# aboutlove.net
KiCad netlist of a schematic drawn in Altium Designer
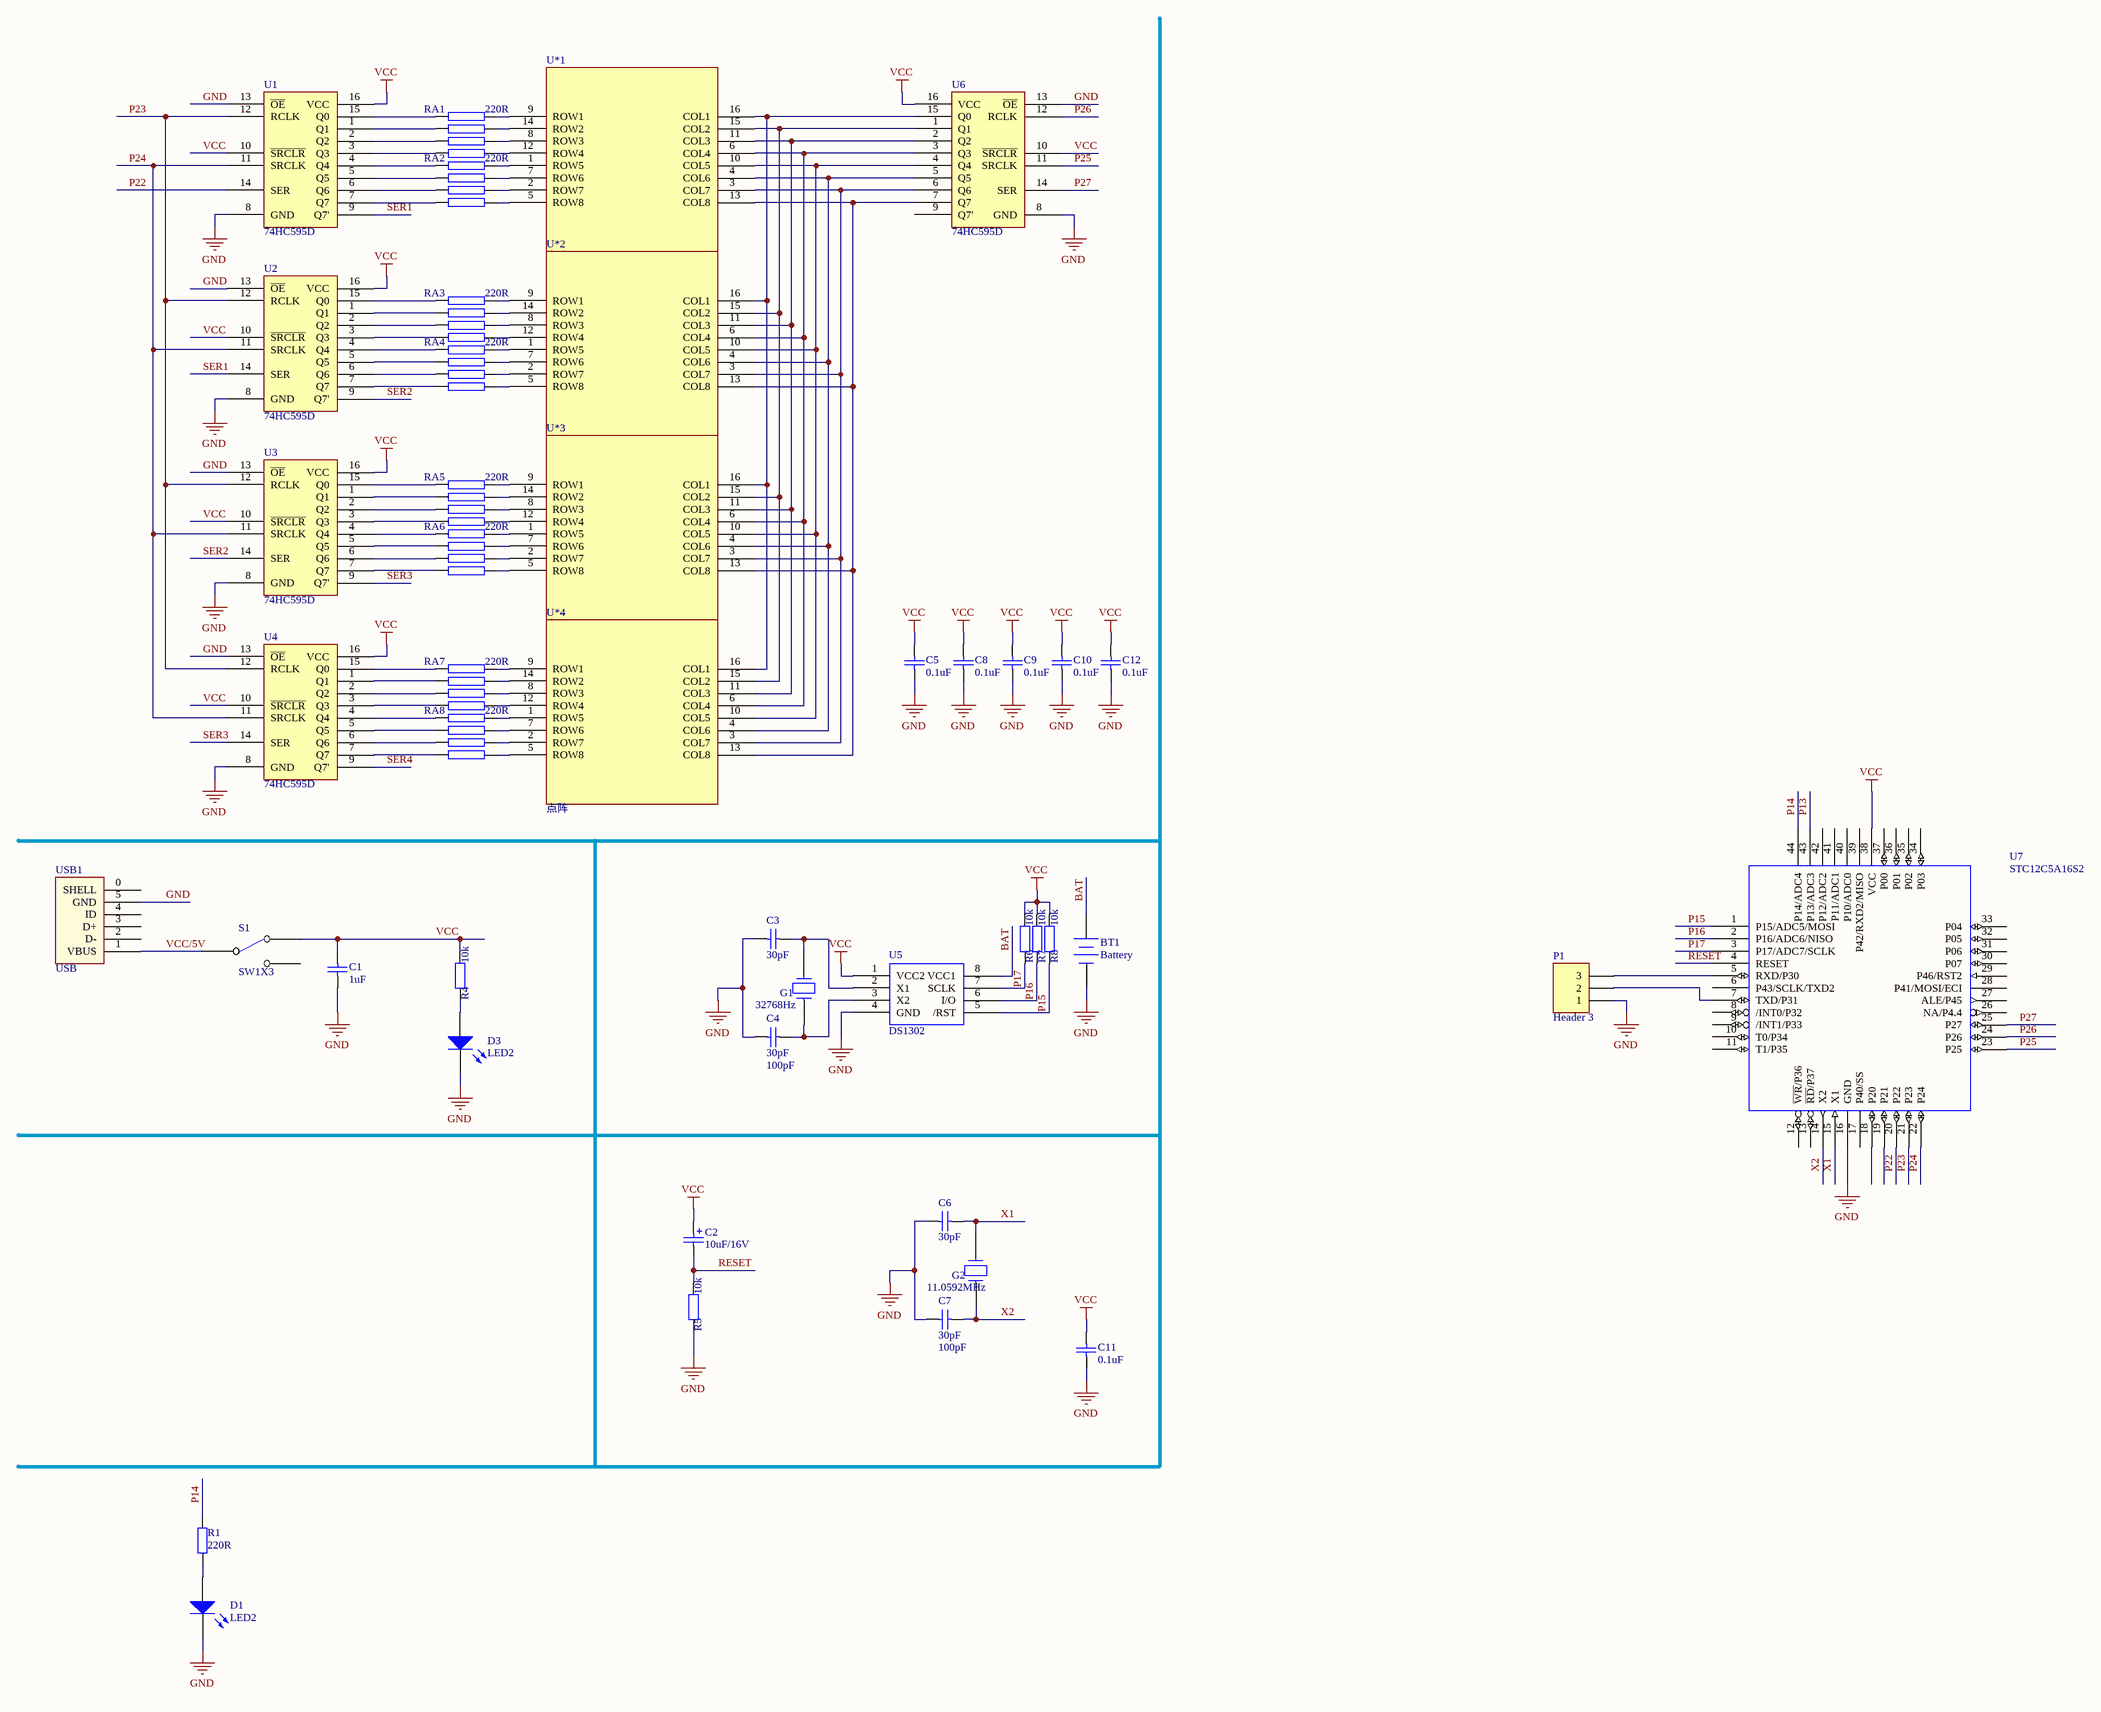
[diagram p0: aboutlove.SchDoc]

(export (version "E")
  (design (tool "Eeschema 10.0.6"))
  (components
    (comp (ref "BT1")
      (value "Battery")
      (footprint "BAT-CR1220")
      (description "Multicell Battery")
      (fields (field (name "PUBLISHER") "Altium Limited"))
      (libsource (lib "Miscellaneous Devices") (part "Battery"))
    )
    (comp (ref "C1")
      (value "1uF")
      (footprint "0805")
      (description "Capacitor")
      (fields (field (name "PUBLISHER") "Altium Limited"))
      (libsource (lib "Miscellaneous Devices") (part "Cap"))
    )
    (comp (ref "C2")
      (value "10uF/16V")
      (footprint "RB.1/.2A")
      (description "Polarized Capacitor (Axial)")
      (fields (field (name "PUBLISHER") "Altium Limited"))
      (libsource (lib "Miscellaneous Devices") (part "Cap Pol2"))
    )
    (comp (ref "C3")
      (value "30pF")
      (footprint "0603_SMALL")
      (description "Capacitor")
      (fields (field (name "PUBLISHER") "Altium Limited"))
      (libsource (lib "Miscellaneous Devices") (part "Cap"))
    )
    (comp (ref "C4")
      (value "30pF")
      (footprint "0603_SMALL")
      (description "Capacitor")
      (fields (field (name "ALTIUM_VALUE") "100pF") (field (name "PUBLISHER") "Altium Limited"))
      (libsource (lib "Miscellaneous Devices") (part "Cap"))
    )
    (comp (ref "C5")
      (value "0.1uF")
      (footprint "0603_SMALL")
      (description "Capacitor")
      (fields (field (name "PUBLISHER") "Altium Limited"))
      (libsource (lib "Miscellaneous Devices") (part "Cap"))
    )
    (comp (ref "C6")
      (value "30pF")
      (footprint "0603_SMALL")
      (description "Capacitor")
      (fields (field (name "PUBLISHER") "Altium Limited"))
      (libsource (lib "Miscellaneous Devices") (part "Cap"))
    )
    (comp (ref "C7")
      (value "30pF")
      (footprint "0603_SMALL")
      (description "Capacitor")
      (fields (field (name "ALTIUM_VALUE") "100pF") (field (name "PUBLISHER") "Altium Limited"))
      (libsource (lib "Miscellaneous Devices") (part "Cap"))
    )
    (comp (ref "C8")
      (value "0.1uF")
      (footprint "0603_SMALL")
      (description "Capacitor")
      (fields (field (name "PUBLISHER") "Altium Limited"))
      (libsource (lib "Miscellaneous Devices") (part "Cap"))
    )
    (comp (ref "C9")
      (value "0.1uF")
      (footprint "0603_SMALL")
      (description "Capacitor")
      (fields (field (name "PUBLISHER") "Altium Limited"))
      (libsource (lib "Miscellaneous Devices") (part "Cap"))
    )
    (comp (ref "C10")
      (value "0.1uF")
      (footprint "0603_SMALL")
      (description "Capacitor")
      (fields (field (name "PUBLISHER") "Altium Limited"))
      (libsource (lib "Miscellaneous Devices") (part "Cap"))
    )
    (comp (ref "C11")
      (value "0.1uF")
      (footprint "0603_SMALL")
      (description "Capacitor")
      (fields (field (name "PUBLISHER") "Altium Limited"))
      (libsource (lib "Miscellaneous Devices") (part "Cap"))
    )
    (comp (ref "C12")
      (value "0.1uF")
      (footprint "0603_SMALL")
      (description "Capacitor")
      (fields (field (name "PUBLISHER") "Altium Limited"))
      (libsource (lib "Miscellaneous Devices") (part "Cap"))
    )
    (comp (ref "D1")
      (value "LED2")
      (footprint "LED0805")
      (description "Typical RED, GREEN, YELLOW, AMBER GaAs LED")
      (fields (field (name "PUBLISHER") "Altium Limited"))
      (libsource (lib "Miscellaneous Devices") (part "LED2"))
    )
    (comp (ref "D3")
      (value "LED2")
      (footprint "LED0805")
      (description "Typical RED, GREEN, YELLOW, AMBER GaAs LED")
      (fields (field (name "PUBLISHER") "Altium Limited"))
      (libsource (lib "Miscellaneous Devices") (part "LED2"))
    )
    (comp (ref "G1")
      (value "32768Hz")
      (footprint "SIP2")
      (description "Crystal")
      (libsource (lib "12C5A60S2") (part "CRYSTAL"))
    )
    (comp (ref "G2")
      (value "11.0592MHz")
      (footprint "XTAL1_ARC")
      (description "Crystal")
      (libsource (lib "12C5A60S2") (part "CRYSTAL"))
    )
    (comp (ref "P1")
      (value "Header 3")
      (footprint "HDR1X3")
      (description "Header, 3-Pin")
      (fields (field (name "PUBLISHER") "Altium Limited"))
      (libsource (lib "Miscellaneous Connectors") (part "Header 3"))
    )
    (comp (ref "R1")
      (value "220R")
      (footprint "0603_SMALL")
      (description "Resistor")
      (fields (field (name "PUBLISHER") "Altium Limited"))
      (libsource (lib "Miscellaneous Devices") (part "Res2"))
    )
    (comp (ref "R4")
      (value "10k")
      (footprint "0805")
      (description "Resistor")
      (fields (field (name "PUBLISHER") "Altium Limited"))
      (libsource (lib "") (part "Res2_1"))
    )
    (comp (ref "R5")
      (value "10k")
      (footprint "0603_SMALL")
      (description "Resistor")
      (fields (field (name "PUBLISHER") "Altium Limited"))
      (libsource (lib "") (part "Res2_1"))
    )
    (comp (ref "R6")
      (value "10k")
      (footprint "0603_SMALL")
      (description "Resistor")
      (fields (field (name "PUBLISHER") "Altium Limited"))
      (libsource (lib "") (part "Res2_1"))
    )
    (comp (ref "R7")
      (value "10k")
      (footprint "0603_SMALL")
      (description "Resistor")
      (fields (field (name "PUBLISHER") "Altium Limited"))
      (libsource (lib "") (part "Res2_1"))
    )
    (comp (ref "R8")
      (value "10k")
      (footprint "0603_SMALL")
      (description "Resistor")
      (fields (field (name "PUBLISHER") "Altium Limited"))
      (libsource (lib "") (part "Res2_1"))
    )
    (comp (ref "RA1") (value "220R") (footprint "NR4_L") (libsource (lib "12C5A60S2") (part "NR4")))
    (comp (ref "RA2") (value "220R") (footprint "NR4_L") (libsource (lib "12C5A60S2") (part "NR4")))
    (comp (ref "RA3") (value "220R") (footprint "NR4_L") (libsource (lib "12C5A60S2") (part "NR4")))
    (comp (ref "RA4") (value "220R") (footprint "NR4_L") (libsource (lib "12C5A60S2") (part "NR4")))
    (comp (ref "RA5") (value "220R") (footprint "NR4_L") (libsource (lib "12C5A60S2") (part "NR4")))
    (comp (ref "RA6") (value "220R") (footprint "NR4_L") (libsource (lib "12C5A60S2") (part "NR4")))
    (comp (ref "RA7") (value "220R") (footprint "NR4_L") (libsource (lib "12C5A60S2") (part "NR4")))
    (comp (ref "RA8") (value "220R") (footprint "NR4_L") (libsource (lib "12C5A60S2") (part "NR4")))
    (comp (ref "S1") (value "SW1X3") (footprint "SW1X3") (libsource (lib "SCHS") (part "SW1X3")))
    (comp (ref "U*1") (value "点阵") (footprint "点阵") (libsource (lib "Jack_SCHS") (part "点阵屏")))
    (comp (ref "U*2") (value "点阵") (footprint "点阵") (libsource (lib "Jack_SCHS") (part "点阵屏")))
    (comp (ref "U*3") (value "点阵") (footprint "点阵") (libsource (lib "Jack_SCHS") (part "点阵屏")))
    (comp (ref "U*4") (value "点阵") (footprint "点阵") (libsource (lib "Jack_SCHS") (part "点阵屏")))
    (comp (ref "U1") (value "74HC595D") (footprint "SOP16") (libsource (lib "") (part "74HC595D_1")))
    (comp (ref "U2") (value "74HC595D") (footprint "SOP16") (libsource (lib "") (part "74HC595D_1")))
    (comp (ref "U3") (value "74HC595D") (footprint "SOP16") (libsource (lib "") (part "74HC595D_1")))
    (comp (ref "U4") (value "74HC595D") (footprint "SOP16") (libsource (lib "") (part "74HC595D_1")))
    (comp (ref "U5") (value "DS1302") (footprint "SOP8") (libsource (lib "SCHS") (part "DS1302")))
    (comp (ref "U6") (value "74HC595D") (footprint "SOP16") (libsource (lib "Jack_SCHS") (part "74HC595D")))
    (comp (ref "U7")
      (value "STC12C5A16S2")
      (footprint "TQFP44")
      (libsource (lib "12C5A60S2") (part "STC12C5A08S2"))
    )
    (comp (ref "USB1") (value "USB") (footprint "USB-MINI") (libsource (lib "元器件封装") (part "USB")))
  )
  (nets
    (net (code "1") (name "/BAT") (class "Default")
      (node (ref "BT1") (pin "1") (pinfunction "+_1") (pintype "passive"))
      (node (ref "U5") (pin "8") (pinfunction "VCC1_8") (pintype "passive"))
    )
    (net (code "2") (name "/P13") (class "Default")
      (node (ref "U7") (pin "43") (pinfunction "P13/ADC3_43") (pintype "passive"))
    )
    (net (code "3") (name "/P14") (class "Default")
      (node (ref "R1") (pin "1") (pinfunction "1_1") (pintype "passive"))
      (node (ref "U7") (pin "44") (pinfunction "P14/ADC4_44") (pintype "passive"))
    )
    (net (code "4") (name "/P15") (class "Default")
      (node (ref "R8") (pin "1") (pinfunction "1_1") (pintype "passive"))
      (node (ref "U5") (pin "5") (pinfunction "/RST_5") (pintype "passive"))
      (node (ref "U7") (pin "1") (pinfunction "P15/ADC5/MOSI_1") (pintype "passive"))
    )
    (net (code "5") (name "/P16") (class "Default")
      (node (ref "R7") (pin "1") (pinfunction "1_1") (pintype "passive"))
      (node (ref "U5") (pin "6") (pinfunction "I/O_6") (pintype "passive"))
      (node (ref "U7") (pin "2") (pinfunction "P16/ADC6/NISO_2") (pintype "passive"))
    )
    (net (code "6") (name "/P17") (class "Default")
      (node (ref "R6") (pin "1") (pinfunction "1_1") (pintype "passive"))
      (node (ref "U5") (pin "7") (pinfunction "SCLK_7") (pintype "passive"))
      (node (ref "U7") (pin "3") (pinfunction "P17/ADC7/SCLK_3") (pintype "passive"))
    )
    (net (code "7") (name "/P22") (class "Default")
      (node (ref "U1") (pin "14") (pinfunction "SER_14") (pintype "passive"))
      (node (ref "U7") (pin "20") (pinfunction "P22_20") (pintype "bidirectional"))
    )
    (net (code "8") (name "/P23") (class "Default")
      (node (ref "U1") (pin "12") (pinfunction "RCLK_12") (pintype "passive"))
      (node (ref "U2") (pin "12") (pinfunction "RCLK_12") (pintype "passive"))
      (node (ref "U3") (pin "12") (pinfunction "RCLK_12") (pintype "passive"))
      (node (ref "U4") (pin "12") (pinfunction "RCLK_12") (pintype "passive"))
      (node (ref "U7") (pin "21") (pinfunction "P23_21") (pintype "bidirectional"))
    )
    (net (code "9") (name "/P24") (class "Default")
      (node (ref "U1") (pin "11") (pinfunction "SRCLK_11") (pintype "passive"))
      (node (ref "U2") (pin "11") (pinfunction "SRCLK_11") (pintype "passive"))
      (node (ref "U3") (pin "11") (pinfunction "SRCLK_11") (pintype "passive"))
      (node (ref "U4") (pin "11") (pinfunction "SRCLK_11") (pintype "passive"))
      (node (ref "U7") (pin "22") (pinfunction "P24_22") (pintype "bidirectional"))
    )
    (net (code "10") (name "/P25") (class "Default")
      (node (ref "U6") (pin "11") (pinfunction "SRCLK_11") (pintype "passive"))
      (node (ref "U7") (pin "23") (pinfunction "P25_23") (pintype "bidirectional"))
    )
    (net (code "11") (name "/P26") (class "Default")
      (node (ref "U6") (pin "12") (pinfunction "RCLK_12") (pintype "passive"))
      (node (ref "U7") (pin "24") (pinfunction "P26_24") (pintype "bidirectional"))
    )
    (net (code "12") (name "/P27") (class "Default")
      (node (ref "U6") (pin "14") (pinfunction "SER_14") (pintype "passive"))
      (node (ref "U7") (pin "25") (pinfunction "P27_25") (pintype "bidirectional"))
    )
    (net (code "13") (name "/RESET") (class "Default")
      (node (ref "C2") (pin "2") (pinfunction "2_2") (pintype "passive"))
      (node (ref "R5") (pin "2") (pinfunction "2_2") (pintype "passive"))
      (node (ref "U7") (pin "4") (pinfunction "RESET_4") (pintype "passive"))
    )
    (net (code "14") (name "/SER1") (class "Default")
      (node (ref "U1") (pin "9") (pinfunction "Q7'_9") (pintype "passive"))
      (node (ref "U2") (pin "14") (pinfunction "SER_14") (pintype "passive"))
    )
    (net (code "15") (name "/SER2") (class "Default")
      (node (ref "U2") (pin "9") (pinfunction "Q7'_9") (pintype "passive"))
      (node (ref "U3") (pin "14") (pinfunction "SER_14") (pintype "passive"))
    )
    (net (code "16") (name "/SER3") (class "Default")
      (node (ref "U3") (pin "9") (pinfunction "Q7'_9") (pintype "passive"))
      (node (ref "U4") (pin "14") (pinfunction "SER_14") (pintype "passive"))
    )
    (net (code "17") (name "/SER4") (class "Default")
      (node (ref "U4") (pin "9") (pinfunction "Q7'_9") (pintype "passive"))
    )
    (net (code "18") (name "/VCC{slash}5V") (class "Default")
      (node (ref "S1") (pin "2") (pintype "passive"))
      (node (ref "USB1") (pin "1") (pinfunction "VBUS_1") (pintype "passive"))
    )
    (net (code "19") (name "/X1") (class "Default")
      (node (ref "C6") (pin "2") (pinfunction "2_2") (pintype "passive"))
      (node (ref "G2") (pin "2") (pinfunction "2_2") (pintype "passive"))
      (node (ref "U7") (pin "15") (pinfunction "X1_15") (pintype "input"))
    )
    (net (code "20") (name "/X2") (class "Default")
      (node (ref "C7") (pin "2") (pinfunction "2_2") (pintype "passive"))
      (node (ref "G2") (pin "1") (pinfunction "1_1") (pintype "passive"))
      (node (ref "U7") (pin "14") (pinfunction "X2_14") (pintype "output"))
    )
    (net (code "21") (name "GND") (class "Default")
      (node (ref "BT1") (pin "2") (pinfunction "-_2") (pintype "passive"))
      (node (ref "C1") (pin "1") (pinfunction "1_1") (pintype "passive"))
      (node (ref "C10") (pin "1") (pinfunction "1_1") (pintype "passive"))
      (node (ref "C11") (pin "1") (pinfunction "1_1") (pintype "passive"))
      (node (ref "C12") (pin "1") (pinfunction "1_1") (pintype "passive"))
      (node (ref "C3") (pin "1") (pinfunction "1_1") (pintype "passive"))
      (node (ref "C4") (pin "1") (pinfunction "1_1") (pintype "passive"))
      (node (ref "C5") (pin "1") (pinfunction "1_1") (pintype "passive"))
      (node (ref "C6") (pin "1") (pinfunction "1_1") (pintype "passive"))
      (node (ref "C7") (pin "1") (pinfunction "1_1") (pintype "passive"))
      (node (ref "C8") (pin "1") (pinfunction "1_1") (pintype "passive"))
      (node (ref "C9") (pin "1") (pinfunction "1_1") (pintype "passive"))
      (node (ref "D1") (pin "2") (pinfunction "K_2") (pintype "passive"))
      (node (ref "D3") (pin "2") (pinfunction "K_2") (pintype "passive"))
      (node (ref "P1") (pin "1") (pinfunction "1_1") (pintype "passive"))
      (node (ref "R5") (pin "1") (pinfunction "1_1") (pintype "passive"))
      (node (ref "U1") (pin "13") (pinfunction "~{OE}_13") (pintype "passive"))
      (node (ref "U1") (pin "8") (pinfunction "GND_8") (pintype "passive"))
      (node (ref "U2") (pin "13") (pinfunction "~{OE}_13") (pintype "passive"))
      (node (ref "U2") (pin "8") (pinfunction "GND_8") (pintype "passive"))
      (node (ref "U3") (pin "13") (pinfunction "~{OE}_13") (pintype "passive"))
      (node (ref "U3") (pin "8") (pinfunction "GND_8") (pintype "passive"))
      (node (ref "U4") (pin "13") (pinfunction "~{OE}_13") (pintype "passive"))
      (node (ref "U4") (pin "8") (pinfunction "GND_8") (pintype "passive"))
      (node (ref "U5") (pin "4") (pinfunction "GND_4") (pintype "passive"))
      (node (ref "U6") (pin "13") (pinfunction "~{OE}_13") (pintype "passive"))
      (node (ref "U6") (pin "8") (pinfunction "GND_8") (pintype "passive"))
      (node (ref "U7") (pin "16") (pinfunction "GND_16") (pintype "power_in"))
      (node (ref "USB1") (pin "5") (pinfunction "GND_5") (pintype "passive"))
    )
    (net (code "22") (name "Net-(D1-A)") (class "Default")
      (node (ref "D1") (pin "1") (pinfunction "A_1") (pintype "passive"))
      (node (ref "R1") (pin "2") (pinfunction "2_2") (pintype "passive"))
    )
    (net (code "23") (name "Net-(D3-A)") (class "Default")
      (node (ref "D3") (pin "1") (pinfunction "A_1") (pintype "passive"))
      (node (ref "R4") (pin "1") (pinfunction "1_1") (pintype "passive"))
    )
    (net (code "24") (name "Net-(U*1-COL1)") (class "Default")
      (node (ref "U*1") (pin "16") (pinfunction "COL1_16") (pintype "passive"))
      (node (ref "U*2") (pin "16") (pinfunction "COL1_16") (pintype "passive"))
      (node (ref "U*3") (pin "16") (pinfunction "COL1_16") (pintype "passive"))
      (node (ref "U*4") (pin "16") (pinfunction "COL1_16") (pintype "passive"))
      (node (ref "U6") (pin "15") (pinfunction "Q0_15") (pintype "passive"))
    )
    (net (code "25") (name "Net-(U*1-COL2)") (class "Default")
      (node (ref "U*1") (pin "15") (pinfunction "COL2_15") (pintype "passive"))
      (node (ref "U*2") (pin "15") (pinfunction "COL2_15") (pintype "passive"))
      (node (ref "U*3") (pin "15") (pinfunction "COL2_15") (pintype "passive"))
      (node (ref "U*4") (pin "15") (pinfunction "COL2_15") (pintype "passive"))
      (node (ref "U6") (pin "1") (pinfunction "Q1_1") (pintype "passive"))
    )
    (net (code "26") (name "Net-(U*1-COL3)") (class "Default")
      (node (ref "U*1") (pin "11") (pinfunction "COL3_11") (pintype "passive"))
      (node (ref "U*2") (pin "11") (pinfunction "COL3_11") (pintype "passive"))
      (node (ref "U*3") (pin "11") (pinfunction "COL3_11") (pintype "passive"))
      (node (ref "U*4") (pin "11") (pinfunction "COL3_11") (pintype "passive"))
      (node (ref "U6") (pin "2") (pinfunction "Q2_2") (pintype "passive"))
    )
    (net (code "27") (name "Net-(U*1-COL4)") (class "Default")
      (node (ref "U*1") (pin "6") (pinfunction "COL4_6") (pintype "passive"))
      (node (ref "U*2") (pin "6") (pinfunction "COL4_6") (pintype "passive"))
      (node (ref "U*3") (pin "6") (pinfunction "COL4_6") (pintype "passive"))
      (node (ref "U*4") (pin "6") (pinfunction "COL4_6") (pintype "passive"))
      (node (ref "U6") (pin "3") (pinfunction "Q3_3") (pintype "passive"))
    )
    (net (code "28") (name "Net-(U*1-COL5)") (class "Default")
      (node (ref "U*1") (pin "10") (pinfunction "COL5_10") (pintype "passive"))
      (node (ref "U*2") (pin "10") (pinfunction "COL5_10") (pintype "passive"))
      (node (ref "U*3") (pin "10") (pinfunction "COL5_10") (pintype "passive"))
      (node (ref "U*4") (pin "10") (pinfunction "COL5_10") (pintype "passive"))
      (node (ref "U6") (pin "4") (pinfunction "Q4_4") (pintype "passive"))
    )
    (net (code "29") (name "Net-(U*1-COL6)") (class "Default")
      (node (ref "U*1") (pin "4") (pinfunction "COL6_4") (pintype "passive"))
      (node (ref "U*2") (pin "4") (pinfunction "COL6_4") (pintype "passive"))
      (node (ref "U*3") (pin "4") (pinfunction "COL6_4") (pintype "passive"))
      (node (ref "U*4") (pin "4") (pinfunction "COL6_4") (pintype "passive"))
      (node (ref "U6") (pin "5") (pinfunction "Q5_5") (pintype "passive"))
    )
    (net (code "30") (name "Net-(U*1-COL7)") (class "Default")
      (node (ref "U*1") (pin "3") (pinfunction "COL7_3") (pintype "passive"))
      (node (ref "U*2") (pin "3") (pinfunction "COL7_3") (pintype "passive"))
      (node (ref "U*3") (pin "3") (pinfunction "COL7_3") (pintype "passive"))
      (node (ref "U*4") (pin "3") (pinfunction "COL7_3") (pintype "passive"))
      (node (ref "U6") (pin "6") (pinfunction "Q6_6") (pintype "passive"))
    )
    (net (code "31") (name "Net-(U*1-COL8)") (class "Default")
      (node (ref "U*1") (pin "13") (pinfunction "COL8_13") (pintype "passive"))
      (node (ref "U*2") (pin "13") (pinfunction "COL8_13") (pintype "passive"))
      (node (ref "U*3") (pin "13") (pinfunction "COL8_13") (pintype "passive"))
      (node (ref "U*4") (pin "13") (pinfunction "COL8_13") (pintype "passive"))
      (node (ref "U6") (pin "7") (pinfunction "Q7_7") (pintype "passive"))
    )
    (net (code "32") (name "Net-(U*1-ROW1)") (class "Default")
      (node (ref "RA1") (pin "4") (pintype "passive"))
      (node (ref "U*1") (pin "9") (pinfunction "ROW1_9") (pintype "passive"))
    )
    (net (code "33") (name "Net-(U*1-ROW2)") (class "Default")
      (node (ref "RA1") (pin "3") (pintype "passive"))
      (node (ref "U*1") (pin "14") (pinfunction "ROW2_14") (pintype "passive"))
    )
    (net (code "34") (name "Net-(U*1-ROW3)") (class "Default")
      (node (ref "RA1") (pin "2") (pintype "passive"))
      (node (ref "U*1") (pin "8") (pinfunction "ROW3_8") (pintype "passive"))
    )
    (net (code "35") (name "Net-(U*1-ROW4)") (class "Default")
      (node (ref "RA1") (pin "1") (pintype "passive"))
      (node (ref "U*1") (pin "12") (pinfunction "ROW4_12") (pintype "passive"))
    )
    (net (code "36") (name "Net-(U*1-ROW5)") (class "Default")
      (node (ref "RA2") (pin "4") (pintype "passive"))
      (node (ref "U*1") (pin "1") (pinfunction "ROW5_1") (pintype "passive"))
    )
    (net (code "37") (name "Net-(U*1-ROW6)") (class "Default")
      (node (ref "RA2") (pin "3") (pintype "passive"))
      (node (ref "U*1") (pin "7") (pinfunction "ROW6_7") (pintype "passive"))
    )
    (net (code "38") (name "Net-(U*1-ROW7)") (class "Default")
      (node (ref "RA2") (pin "2") (pintype "passive"))
      (node (ref "U*1") (pin "2") (pinfunction "ROW7_2") (pintype "passive"))
    )
    (net (code "39") (name "Net-(U*1-ROW8)") (class "Default")
      (node (ref "RA2") (pin "1") (pintype "passive"))
      (node (ref "U*1") (pin "5") (pinfunction "ROW8_5") (pintype "passive"))
    )
    (net (code "40") (name "Net-(U*2-ROW1)") (class "Default")
      (node (ref "RA3") (pin "4") (pintype "passive"))
      (node (ref "U*2") (pin "9") (pinfunction "ROW1_9") (pintype "passive"))
    )
    (net (code "41") (name "Net-(U*2-ROW2)") (class "Default")
      (node (ref "RA3") (pin "3") (pintype "passive"))
      (node (ref "U*2") (pin "14") (pinfunction "ROW2_14") (pintype "passive"))
    )
    (net (code "42") (name "Net-(U*2-ROW3)") (class "Default")
      (node (ref "RA3") (pin "2") (pintype "passive"))
      (node (ref "U*2") (pin "8") (pinfunction "ROW3_8") (pintype "passive"))
    )
    (net (code "43") (name "Net-(U*2-ROW4)") (class "Default")
      (node (ref "RA3") (pin "1") (pintype "passive"))
      (node (ref "U*2") (pin "12") (pinfunction "ROW4_12") (pintype "passive"))
    )
    (net (code "44") (name "Net-(U*2-ROW5)") (class "Default")
      (node (ref "RA4") (pin "4") (pintype "passive"))
      (node (ref "U*2") (pin "1") (pinfunction "ROW5_1") (pintype "passive"))
    )
    (net (code "45") (name "Net-(U*2-ROW6)") (class "Default")
      (node (ref "RA4") (pin "3") (pintype "passive"))
      (node (ref "U*2") (pin "7") (pinfunction "ROW6_7") (pintype "passive"))
    )
    (net (code "46") (name "Net-(U*2-ROW7)") (class "Default")
      (node (ref "RA4") (pin "2") (pintype "passive"))
      (node (ref "U*2") (pin "2") (pinfunction "ROW7_2") (pintype "passive"))
    )
    (net (code "47") (name "Net-(U*2-ROW8)") (class "Default")
      (node (ref "RA4") (pin "1") (pintype "passive"))
      (node (ref "U*2") (pin "5") (pinfunction "ROW8_5") (pintype "passive"))
    )
    (net (code "48") (name "Net-(U*3-ROW1)") (class "Default")
      (node (ref "RA5") (pin "4") (pintype "passive"))
      (node (ref "U*3") (pin "9") (pinfunction "ROW1_9") (pintype "passive"))
    )
    (net (code "49") (name "Net-(U*3-ROW2)") (class "Default")
      (node (ref "RA5") (pin "3") (pintype "passive"))
      (node (ref "U*3") (pin "14") (pinfunction "ROW2_14") (pintype "passive"))
    )
    (net (code "50") (name "Net-(U*3-ROW3)") (class "Default")
      (node (ref "RA5") (pin "2") (pintype "passive"))
      (node (ref "U*3") (pin "8") (pinfunction "ROW3_8") (pintype "passive"))
    )
    (net (code "51") (name "Net-(U*3-ROW4)") (class "Default")
      (node (ref "RA5") (pin "1") (pintype "passive"))
      (node (ref "U*3") (pin "12") (pinfunction "ROW4_12") (pintype "passive"))
    )
    (net (code "52") (name "Net-(U*3-ROW5)") (class "Default")
      (node (ref "RA6") (pin "4") (pintype "passive"))
      (node (ref "U*3") (pin "1") (pinfunction "ROW5_1") (pintype "passive"))
    )
    (net (code "53") (name "Net-(U*3-ROW6)") (class "Default")
      (node (ref "RA6") (pin "3") (pintype "passive"))
      (node (ref "U*3") (pin "7") (pinfunction "ROW6_7") (pintype "passive"))
    )
    (net (code "54") (name "Net-(U*3-ROW7)") (class "Default")
      (node (ref "RA6") (pin "2") (pintype "passive"))
      (node (ref "U*3") (pin "2") (pinfunction "ROW7_2") (pintype "passive"))
    )
    (net (code "55") (name "Net-(U*3-ROW8)") (class "Default")
      (node (ref "RA6") (pin "1") (pintype "passive"))
      (node (ref "U*3") (pin "5") (pinfunction "ROW8_5") (pintype "passive"))
    )
    (net (code "56") (name "Net-(U*4-ROW1)") (class "Default")
      (node (ref "RA7") (pin "4") (pintype "passive"))
      (node (ref "U*4") (pin "9") (pinfunction "ROW1_9") (pintype "passive"))
    )
    (net (code "57") (name "Net-(U*4-ROW2)") (class "Default")
      (node (ref "RA7") (pin "3") (pintype "passive"))
      (node (ref "U*4") (pin "14") (pinfunction "ROW2_14") (pintype "passive"))
    )
    (net (code "58") (name "Net-(U*4-ROW3)") (class "Default")
      (node (ref "RA7") (pin "2") (pintype "passive"))
      (node (ref "U*4") (pin "8") (pinfunction "ROW3_8") (pintype "passive"))
    )
    (net (code "59") (name "Net-(U*4-ROW4)") (class "Default")
      (node (ref "RA7") (pin "1") (pintype "passive"))
      (node (ref "U*4") (pin "12") (pinfunction "ROW4_12") (pintype "passive"))
    )
    (net (code "60") (name "Net-(U*4-ROW5)") (class "Default")
      (node (ref "RA8") (pin "4") (pintype "passive"))
      (node (ref "U*4") (pin "1") (pinfunction "ROW5_1") (pintype "passive"))
    )
    (net (code "61") (name "Net-(U*4-ROW6)") (class "Default")
      (node (ref "RA8") (pin "3") (pintype "passive"))
      (node (ref "U*4") (pin "7") (pinfunction "ROW6_7") (pintype "passive"))
    )
    (net (code "62") (name "Net-(U*4-ROW7)") (class "Default")
      (node (ref "RA8") (pin "2") (pintype "passive"))
      (node (ref "U*4") (pin "2") (pinfunction "ROW7_2") (pintype "passive"))
    )
    (net (code "63") (name "Net-(U*4-ROW8)") (class "Default")
      (node (ref "RA8") (pin "1") (pintype "passive"))
      (node (ref "U*4") (pin "5") (pinfunction "ROW8_5") (pintype "passive"))
    )
    (net (code "64") (name "Net-(U1-Q0)") (class "Default")
      (node (ref "RA1") (pin "5") (pintype "passive"))
      (node (ref "U1") (pin "15") (pinfunction "Q0_15") (pintype "passive"))
    )
    (net (code "65") (name "Net-(U1-Q1)") (class "Default")
      (node (ref "RA1") (pin "6") (pintype "passive"))
      (node (ref "U1") (pin "1") (pinfunction "Q1_1") (pintype "passive"))
    )
    (net (code "66") (name "Net-(U1-Q2)") (class "Default")
      (node (ref "RA1") (pin "7") (pintype "passive"))
      (node (ref "U1") (pin "2") (pinfunction "Q2_2") (pintype "passive"))
    )
    (net (code "67") (name "Net-(U1-Q3)") (class "Default")
      (node (ref "RA1") (pin "8") (pintype "passive"))
      (node (ref "U1") (pin "3") (pinfunction "Q3_3") (pintype "passive"))
    )
    (net (code "68") (name "Net-(U1-Q4)") (class "Default")
      (node (ref "RA2") (pin "5") (pintype "passive"))
      (node (ref "U1") (pin "4") (pinfunction "Q4_4") (pintype "passive"))
    )
    (net (code "69") (name "Net-(U1-Q5)") (class "Default")
      (node (ref "RA2") (pin "6") (pintype "passive"))
      (node (ref "U1") (pin "5") (pinfunction "Q5_5") (pintype "passive"))
    )
    (net (code "70") (name "Net-(U1-Q6)") (class "Default")
      (node (ref "RA2") (pin "7") (pintype "passive"))
      (node (ref "U1") (pin "6") (pinfunction "Q6_6") (pintype "passive"))
    )
    (net (code "71") (name "Net-(U1-Q7)") (class "Default")
      (node (ref "RA2") (pin "8") (pintype "passive"))
      (node (ref "U1") (pin "7") (pinfunction "Q7_7") (pintype "passive"))
    )
    (net (code "72") (name "Net-(U2-Q0)") (class "Default")
      (node (ref "RA3") (pin "5") (pintype "passive"))
      (node (ref "U2") (pin "15") (pinfunction "Q0_15") (pintype "passive"))
    )
    (net (code "73") (name "Net-(U2-Q1)") (class "Default")
      (node (ref "RA3") (pin "6") (pintype "passive"))
      (node (ref "U2") (pin "1") (pinfunction "Q1_1") (pintype "passive"))
    )
    (net (code "74") (name "Net-(U2-Q2)") (class "Default")
      (node (ref "RA3") (pin "7") (pintype "passive"))
      (node (ref "U2") (pin "2") (pinfunction "Q2_2") (pintype "passive"))
    )
    (net (code "75") (name "Net-(U2-Q3)") (class "Default")
      (node (ref "RA3") (pin "8") (pintype "passive"))
      (node (ref "U2") (pin "3") (pinfunction "Q3_3") (pintype "passive"))
    )
    (net (code "76") (name "Net-(U2-Q4)") (class "Default")
      (node (ref "RA4") (pin "5") (pintype "passive"))
      (node (ref "U2") (pin "4") (pinfunction "Q4_4") (pintype "passive"))
    )
    (net (code "77") (name "Net-(U2-Q5)") (class "Default")
      (node (ref "RA4") (pin "6") (pintype "passive"))
      (node (ref "U2") (pin "5") (pinfunction "Q5_5") (pintype "passive"))
    )
    (net (code "78") (name "Net-(U2-Q6)") (class "Default")
      (node (ref "RA4") (pin "7") (pintype "passive"))
      (node (ref "U2") (pin "6") (pinfunction "Q6_6") (pintype "passive"))
    )
    (net (code "79") (name "Net-(U2-Q7)") (class "Default")
      (node (ref "RA4") (pin "8") (pintype "passive"))
      (node (ref "U2") (pin "7") (pinfunction "Q7_7") (pintype "passive"))
    )
    (net (code "80") (name "Net-(U3-Q0)") (class "Default")
      (node (ref "RA5") (pin "5") (pintype "passive"))
      (node (ref "U3") (pin "15") (pinfunction "Q0_15") (pintype "passive"))
    )
    (net (code "81") (name "Net-(U3-Q1)") (class "Default")
      (node (ref "RA5") (pin "6") (pintype "passive"))
      (node (ref "U3") (pin "1") (pinfunction "Q1_1") (pintype "passive"))
    )
    (net (code "82") (name "Net-(U3-Q2)") (class "Default")
      (node (ref "RA5") (pin "7") (pintype "passive"))
      (node (ref "U3") (pin "2") (pinfunction "Q2_2") (pintype "passive"))
    )
    (net (code "83") (name "Net-(U3-Q3)") (class "Default")
      (node (ref "RA5") (pin "8") (pintype "passive"))
      (node (ref "U3") (pin "3") (pinfunction "Q3_3") (pintype "passive"))
    )
    (net (code "84") (name "Net-(U3-Q4)") (class "Default")
      (node (ref "RA6") (pin "5") (pintype "passive"))
      (node (ref "U3") (pin "4") (pinfunction "Q4_4") (pintype "passive"))
    )
    (net (code "85") (name "Net-(U3-Q5)") (class "Default")
      (node (ref "RA6") (pin "6") (pintype "passive"))
      (node (ref "U3") (pin "5") (pinfunction "Q5_5") (pintype "passive"))
    )
    (net (code "86") (name "Net-(U3-Q6)") (class "Default")
      (node (ref "RA6") (pin "7") (pintype "passive"))
      (node (ref "U3") (pin "6") (pinfunction "Q6_6") (pintype "passive"))
    )
    (net (code "87") (name "Net-(U3-Q7)") (class "Default")
      (node (ref "RA6") (pin "8") (pintype "passive"))
      (node (ref "U3") (pin "7") (pinfunction "Q7_7") (pintype "passive"))
    )
    (net (code "88") (name "Net-(U4-Q0)") (class "Default")
      (node (ref "RA7") (pin "5") (pintype "passive"))
      (node (ref "U4") (pin "15") (pinfunction "Q0_15") (pintype "passive"))
    )
    (net (code "89") (name "Net-(U4-Q1)") (class "Default")
      (node (ref "RA7") (pin "6") (pintype "passive"))
      (node (ref "U4") (pin "1") (pinfunction "Q1_1") (pintype "passive"))
    )
    (net (code "90") (name "Net-(U4-Q2)") (class "Default")
      (node (ref "RA7") (pin "7") (pintype "passive"))
      (node (ref "U4") (pin "2") (pinfunction "Q2_2") (pintype "passive"))
    )
    (net (code "91") (name "Net-(U4-Q3)") (class "Default")
      (node (ref "RA7") (pin "8") (pintype "passive"))
      (node (ref "U4") (pin "3") (pinfunction "Q3_3") (pintype "passive"))
    )
    (net (code "92") (name "Net-(U4-Q4)") (class "Default")
      (node (ref "RA8") (pin "5") (pintype "passive"))
      (node (ref "U4") (pin "4") (pinfunction "Q4_4") (pintype "passive"))
    )
    (net (code "93") (name "Net-(U4-Q5)") (class "Default")
      (node (ref "RA8") (pin "6") (pintype "passive"))
      (node (ref "U4") (pin "5") (pinfunction "Q5_5") (pintype "passive"))
    )
    (net (code "94") (name "Net-(U4-Q6)") (class "Default")
      (node (ref "RA8") (pin "7") (pintype "passive"))
      (node (ref "U4") (pin "6") (pinfunction "Q6_6") (pintype "passive"))
    )
    (net (code "95") (name "Net-(U4-Q7)") (class "Default")
      (node (ref "RA8") (pin "8") (pintype "passive"))
      (node (ref "U4") (pin "7") (pinfunction "Q7_7") (pintype "passive"))
    )
    (net (code "96") (name "Net-(U5-X1)") (class "Default")
      (node (ref "C3") (pin "2") (pinfunction "2_2") (pintype "passive"))
      (node (ref "G1") (pin "2") (pinfunction "2_2") (pintype "passive"))
      (node (ref "U5") (pin "2") (pinfunction "X1_2") (pintype "passive"))
    )
    (net (code "97") (name "Net-(U5-X2)") (class "Default")
      (node (ref "C4") (pin "2") (pinfunction "2_2") (pintype "passive"))
      (node (ref "G1") (pin "1") (pinfunction "1_1") (pintype "passive"))
      (node (ref "U5") (pin "3") (pinfunction "X2_3") (pintype "passive"))
    )
    (net (code "98") (name "Net-(U7-RXD{slash}P30)") (class "Default")
      (node (ref "P1") (pin "3") (pinfunction "3_3") (pintype "passive"))
      (node (ref "U7") (pin "5") (pinfunction "RXD/P30_5") (pintype "bidirectional"))
    )
    (net (code "99") (name "Net-(U7-TXD{slash}P31)") (class "Default")
      (node (ref "P1") (pin "2") (pinfunction "2_2") (pintype "passive"))
      (node (ref "U7") (pin "7") (pinfunction "TXD/P31_7") (pintype "bidirectional"))
    )
    (net (code "100") (name "VCC") (class "Default")
      (node (ref "C1") (pin "2") (pinfunction "2_2") (pintype "passive"))
      (node (ref "C10") (pin "2") (pinfunction "2_2") (pintype "passive"))
      (node (ref "C11") (pin "2") (pinfunction "2_2") (pintype "passive"))
      (node (ref "C12") (pin "2") (pinfunction "2_2") (pintype "passive"))
      (node (ref "C2") (pin "1") (pinfunction "1_1") (pintype "passive"))
      (node (ref "C5") (pin "2") (pinfunction "2_2") (pintype "passive"))
      (node (ref "C8") (pin "2") (pinfunction "2_2") (pintype "passive"))
      (node (ref "C9") (pin "2") (pinfunction "2_2") (pintype "passive"))
      (node (ref "R4") (pin "2") (pinfunction "2_2") (pintype "passive"))
      (node (ref "R6") (pin "2") (pinfunction "2_2") (pintype "passive"))
      (node (ref "R7") (pin "2") (pinfunction "2_2") (pintype "passive"))
      (node (ref "R8") (pin "2") (pinfunction "2_2") (pintype "passive"))
      (node (ref "S1") (pin "1") (pintype "passive"))
      (node (ref "U1") (pin "10") (pinfunction "~{SRCLR}_10") (pintype "passive"))
      (node (ref "U1") (pin "16") (pinfunction "VCC_16") (pintype "passive"))
      (node (ref "U2") (pin "10") (pinfunction "~{SRCLR}_10") (pintype "passive"))
      (node (ref "U2") (pin "16") (pinfunction "VCC_16") (pintype "passive"))
      (node (ref "U3") (pin "10") (pinfunction "~{SRCLR}_10") (pintype "passive"))
      (node (ref "U3") (pin "16") (pinfunction "VCC_16") (pintype "passive"))
      (node (ref "U4") (pin "10") (pinfunction "~{SRCLR}_10") (pintype "passive"))
      (node (ref "U4") (pin "16") (pinfunction "VCC_16") (pintype "passive"))
      (node (ref "U5") (pin "1") (pinfunction "VCC2_1") (pintype "passive"))
      (node (ref "U6") (pin "10") (pinfunction "~{SRCLR}_10") (pintype "passive"))
      (node (ref "U6") (pin "16") (pinfunction "VCC_16") (pintype "passive"))
      (node (ref "U7") (pin "38") (pinfunction "VCC_38") (pintype "passive"))
    )
    (net (code "101") (name "unconnected-(S1-Pad3)") (class "Default")
      (node (ref "S1") (pin "3") (pintype "passive"))
    )
    (net (code "102") (name "unconnected-(U6-Q7'-Pad9)") (class "Default")
      (node (ref "U6") (pin "9") (pinfunction "Q7'_9") (pintype "passive"))
    )
    (net (code "103") (name "unconnected-(U7-ALE{slash}P45-Pad27)") (class "Default")
      (node (ref "U7") (pin "27") (pinfunction "ALE/P45_27") (pintype "output"))
    )
    (net (code "104") (name "unconnected-(U7-NA{slash}P4.4-Pad26)") (class "Default")
      (node (ref "U7") (pin "26") (pinfunction "NA/P4.4_26") (pintype "output"))
    )
    (net (code "105") (name "unconnected-(U7-P00-Pad37)") (class "Default")
      (node (ref "U7") (pin "37") (pinfunction "P00_37") (pintype "bidirectional"))
    )
    (net (code "106") (name "unconnected-(U7-P01-Pad36)") (class "Default")
      (node (ref "U7") (pin "36") (pinfunction "P01_36") (pintype "bidirectional"))
    )
    (net (code "107") (name "unconnected-(U7-P02-Pad35)") (class "Default")
      (node (ref "U7") (pin "35") (pinfunction "P02_35") (pintype "bidirectional"))
    )
    (net (code "108") (name "unconnected-(U7-P03-Pad34)") (class "Default")
      (node (ref "U7") (pin "34") (pinfunction "P03_34") (pintype "bidirectional"))
    )
    (net (code "109") (name "unconnected-(U7-P04-Pad33)") (class "Default")
      (node (ref "U7") (pin "33") (pinfunction "P04_33") (pintype "bidirectional"))
    )
    (net (code "110") (name "unconnected-(U7-P05-Pad32)") (class "Default")
      (node (ref "U7") (pin "32") (pinfunction "P05_32") (pintype "bidirectional"))
    )
    (net (code "111") (name "unconnected-(U7-P06-Pad31)") (class "Default")
      (node (ref "U7") (pin "31") (pinfunction "P06_31") (pintype "bidirectional"))
    )
    (net (code "112") (name "unconnected-(U7-P07-Pad30)") (class "Default")
      (node (ref "U7") (pin "30") (pinfunction "P07_30") (pintype "bidirectional"))
    )
    (net (code "113") (name "unconnected-(U7-P10{slash}ADC0-Pad40)") (class "Default")
      (node (ref "U7") (pin "40") (pinfunction "P10/ADC0_40") (pintype "passive"))
    )
    (net (code "114") (name "unconnected-(U7-P11{slash}ADC1-Pad41)") (class "Default")
      (node (ref "U7") (pin "41") (pinfunction "P11/ADC1_41") (pintype "passive"))
    )
    (net (code "115") (name "unconnected-(U7-P12{slash}ADC2-Pad42)") (class "Default")
      (node (ref "U7") (pin "42") (pinfunction "P12/ADC2_42") (pintype "passive"))
    )
    (net (code "116") (name "unconnected-(U7-P20-Pad18)") (class "Default")
      (node (ref "U7") (pin "18") (pinfunction "P20_18") (pintype "bidirectional"))
    )
    (net (code "117") (name "unconnected-(U7-P21-Pad19)") (class "Default")
      (node (ref "U7") (pin "19") (pinfunction "P21_19") (pintype "bidirectional"))
    )
    (net (code "118") (name "unconnected-(U7-P40{slash}SS-Pad17)") (class "Default")
      (node (ref "U7") (pin "17") (pinfunction "P40/SS_17") (pintype "passive"))
    )
    (net (code "119") (name "unconnected-(U7-P41{slash}MOSI{slash}ECI-Pad28)") (class "Default")
      (node (ref "U7") (pin "28") (pinfunction "P41/MOSI/ECI_28") (pintype "passive"))
    )
    (net (code "120") (name "unconnected-(U7-P42{slash}RXD2{slash}MISO-Pad39)") (class "Default")
      (node (ref "U7") (pin "39") (pinfunction "P42/RXD2/MISO_39") (pintype "passive"))
    )
    (net (code "121") (name "unconnected-(U7-P43{slash}SCLK{slash}TXD2-Pad6)") (class "Default")
      (node (ref "U7") (pin "6") (pinfunction "P43/SCLK/TXD2_6") (pintype "passive"))
    )
    (net (code "122") (name "unconnected-(U7-P46{slash}RST2-Pad29)") (class "Default")
      (node (ref "U7") (pin "29") (pinfunction "P46/RST2_29") (pintype "input"))
    )
    (net (code "123") (name "unconnected-(U7-T0{slash}P34-Pad10)") (class "Default")
      (node (ref "U7") (pin "10") (pinfunction "T0/P34_10") (pintype "bidirectional"))
    )
    (net (code "124") (name "unconnected-(U7-T1{slash}P35-Pad11)") (class "Default")
      (node (ref "U7") (pin "11") (pinfunction "T1/P35_11") (pintype "bidirectional"))
    )
    (net (code "125") (name "unconnected-(U7-{slash}INT0{slash}P32-Pad8)") (class "Default")
      (node (ref "U7") (pin "8") (pinfunction "/INT0/P32_8") (pintype "bidirectional"))
    )
    (net (code "126") (name "unconnected-(U7-{slash}INT1{slash}P33-Pad9)") (class "Default")
      (node (ref "U7") (pin "9") (pinfunction "/INT1/P33_9") (pintype "bidirectional"))
    )
    (net (code "127") (name "unconnected-(U7-~{RD}{slash}P37-Pad13)") (class "Default")
      (node (ref "U7") (pin "13") (pinfunction "~{RD}/P37_13") (pintype "bidirectional"))
    )
    (net (code "128") (name "unconnected-(U7-~{WR}{slash}P36-Pad12)") (class "Default")
      (node (ref "U7") (pin "12") (pinfunction "~{WR}/P36_12") (pintype "bidirectional"))
    )
    (net (code "129") (name "unconnected-(USB1-D+-Pad3)") (class "Default")
      (node (ref "USB1") (pin "3") (pinfunction "D+_3") (pintype "passive"))
    )
    (net (code "130") (name "unconnected-(USB1-D--Pad2)") (class "Default")
      (node (ref "USB1") (pin "2") (pinfunction "D-_2") (pintype "passive"))
    )
    (net (code "131") (name "unconnected-(USB1-ID-Pad4)") (class "Default")
      (node (ref "USB1") (pin "4") (pinfunction "ID_4") (pintype "passive"))
    )
    (net (code "132") (name "unconnected-(USB1-SHELL-Pad0)") (class "Default")
      (node (ref "USB1") (pin "0") (pinfunction "SHELL_0") (pintype "passive"))
    )
  )
)
